# rapidshark-main-breakout-mk-1_0.net
KiCad netlist of a schematic drawn in EAGLE
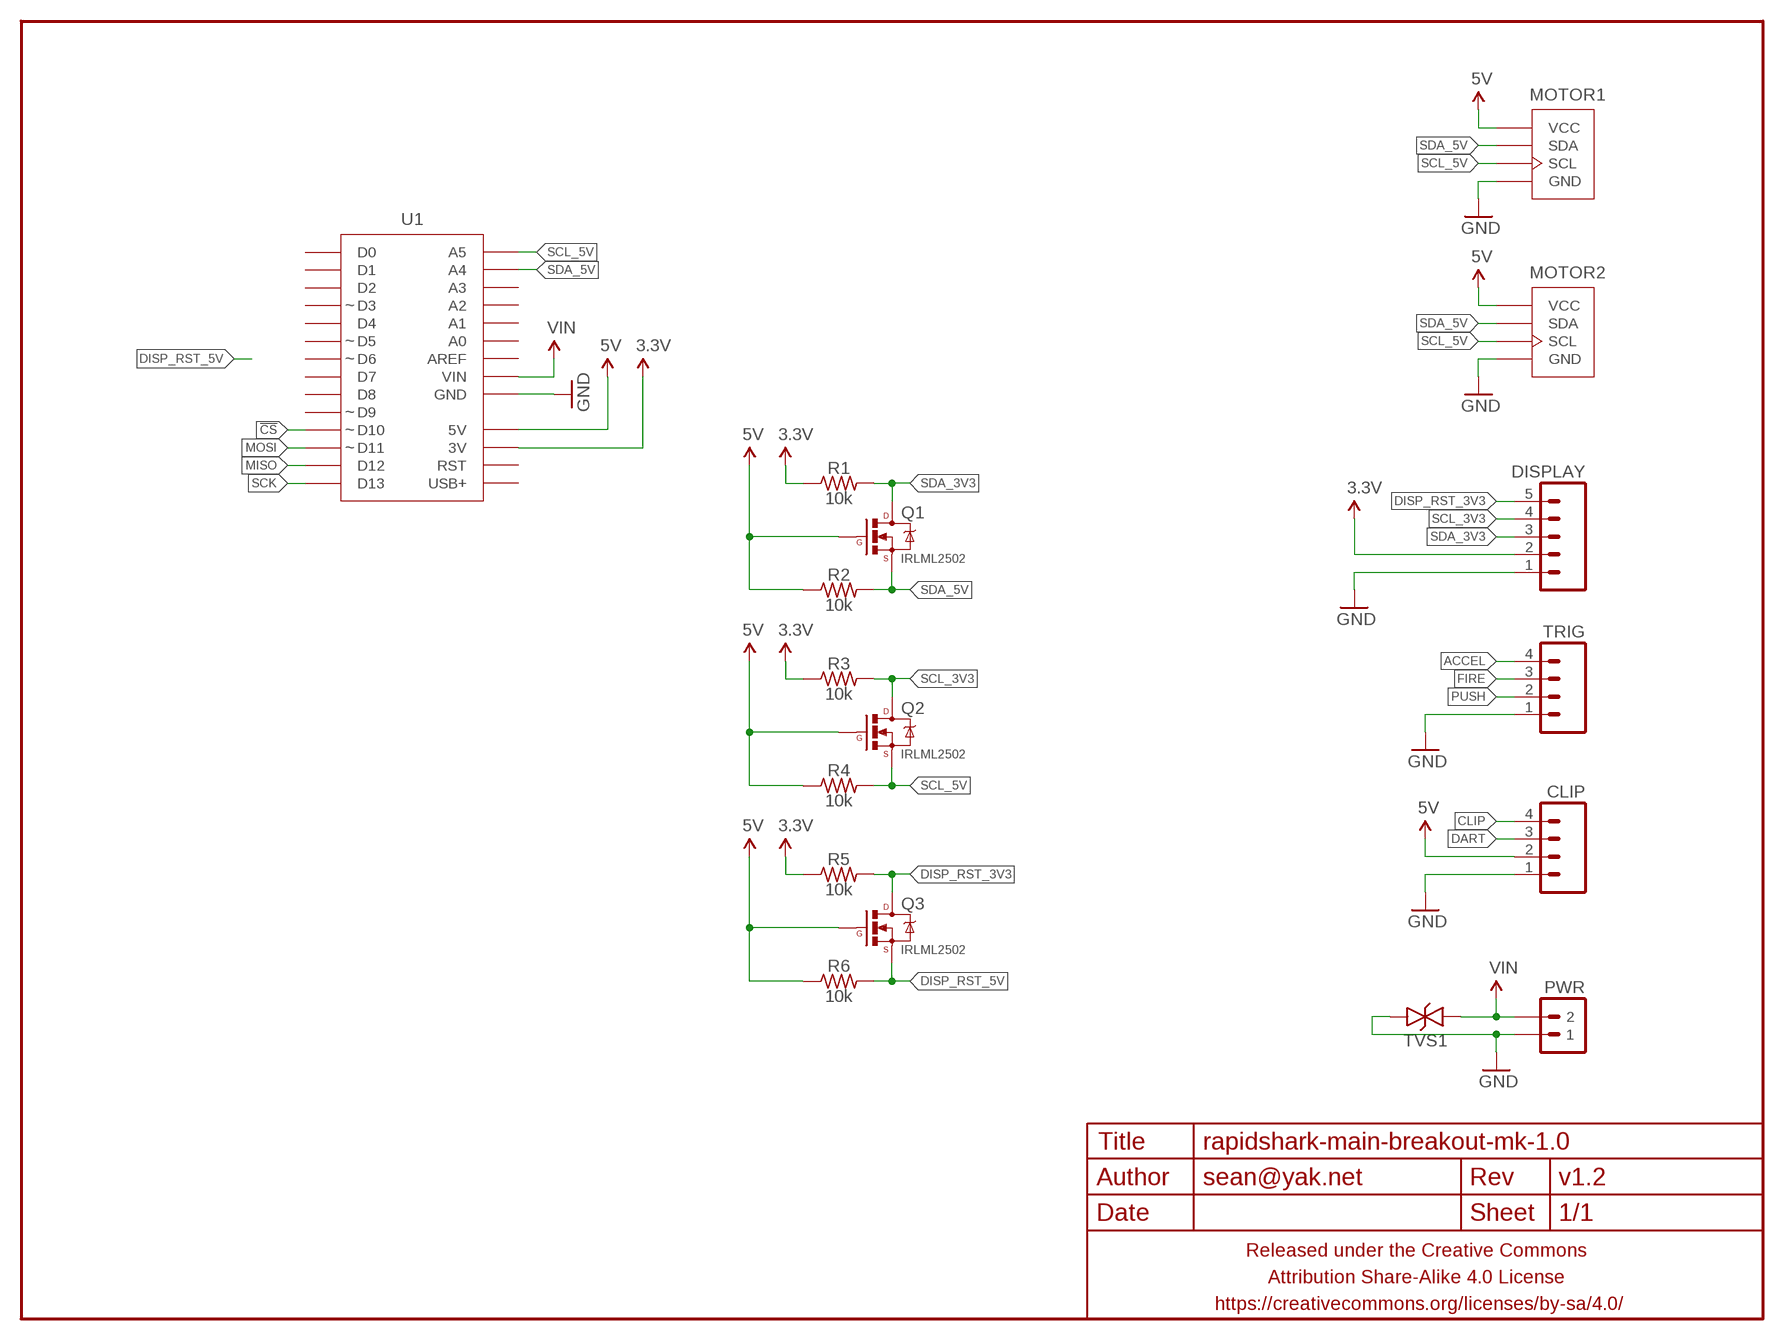
[diagram p0: schematic, sheet 1]

(export (version "E")
  (design (tool "Eeschema 10.0.6"))
  (components
    (comp (ref "CLIP")
      (value "M04JST-PTH-VERT")
      (footprint "eagle-import:JST-4-PH-VERT-PTH")
      (libsource (lib "eagle-import") (part "M04JST-PTH-VERT"))
    )
    (comp (ref "DISPLAY")
      (value "M05JST-PH-VERT-PTH")
      (footprint "eagle-import:JST-5-PH-VERT-PTH")
      (libsource (lib "eagle-import") (part "M05JST-PH-VERT-PTH"))
    )
    (comp (ref "FRAME1")
      (value "FRAME-LETTERNO_PACKAGE")
      (footprint "eagle-import:DUMMY")
      (fields (field (name "DESIGNER") "sean@yak.net") (field (name "VERSION") "v1.2"))
      (libsource (lib "eagle-import") (part "FRAME-LETTERNO_PACKAGE"))
    )
    (comp (ref "MOTOR1")
      (value "M04-I2CJST-4-PH-VERT-NS")
      (footprint "eagle-import:JST-4-PH-VERT-PTH")
      (libsource (lib "eagle-import") (part "M04-I2CJST-4-PH-VERT-NS"))
    )
    (comp (ref "MOTOR2")
      (value "M04-I2CJST-4-PH-VERT-NS")
      (footprint "eagle-import:JST-4-PH-VERT-PTH")
      (libsource (lib "eagle-import") (part "M04-I2CJST-4-PH-VERT-NS"))
    )
    (comp (ref "PWR")
      (value "M02PTH-CENTERED-R+")
      (footprint "eagle-import:1X02-CENTER-R+")
      (libsource (lib "eagle-import") (part "M02PTH-CENTERED-R+"))
    )
    (comp (ref "Q1")
      (value "IRLML2502")
      (footprint "eagle-import:SOT23")
      (libsource (lib "eagle-import") (part "MOSFET-NCHANNELIRLML2502"))
    )
    (comp (ref "Q2")
      (value "IRLML2502")
      (footprint "eagle-import:SOT23")
      (libsource (lib "eagle-import") (part "MOSFET-NCHANNELIRLML2502"))
    )
    (comp (ref "Q3")
      (value "IRLML2502")
      (footprint "eagle-import:SOT23")
      (libsource (lib "eagle-import") (part "MOSFET-NCHANNELIRLML2502"))
    )
    (comp (ref "R1")
      (value "10k")
      (footprint "eagle-import:R0603")
      (libsource (lib "eagle-import") (part "RESISTORR0603"))
    )
    (comp (ref "R2")
      (value "10k")
      (footprint "eagle-import:R0603")
      (libsource (lib "eagle-import") (part "RESISTORR0603"))
    )
    (comp (ref "R3")
      (value "10k")
      (footprint "eagle-import:R0603")
      (libsource (lib "eagle-import") (part "RESISTORR0603"))
    )
    (comp (ref "R4")
      (value "10k")
      (footprint "eagle-import:R0603")
      (libsource (lib "eagle-import") (part "RESISTORR0603"))
    )
    (comp (ref "R5")
      (value "10k")
      (footprint "eagle-import:R0603")
      (libsource (lib "eagle-import") (part "RESISTORR0603"))
    )
    (comp (ref "R6")
      (value "10k")
      (footprint "eagle-import:R0603")
      (libsource (lib "eagle-import") (part "RESISTORR0603"))
    )
    (comp (ref "TRIG")
      (value "M04JST-PTH-VERT")
      (footprint "eagle-import:JST-4-PH-VERT-PTH")
      (libsource (lib "eagle-import") (part "M04JST-PTH-VERT"))
    )
    (comp (ref "TVS1")
      (value "TVSSMA")
      (footprint "eagle-import:SMA-DIODE-TVS-BIDIR")
      (libsource (lib "eagle-import") (part "TVSSMA"))
    )
    (comp (ref "U1")
      (value "ADAFRUIT_METRO_MINISMD-NOHOLES")
      (footprint "eagle-import:ADAFRUIT_METRO_MINI_SMD")
      (libsource (lib "eagle-import") (part "ADAFRUIT_METRO_MINISMD-NOHOLES"))
    )
  )
  (nets
    (net (code "1") (name "/~{CS}") (class "Default")
      (node (ref "U1") (pin "11") (pinfunction "D10_11") (pintype "bidirectional"))
    )
    (net (code "2") (name "3.3V") (class "Default")
      (node (ref "DISPLAY") (pin "2") (pinfunction "2_2") (pintype "passive"))
      (node (ref "R1") (pin "1") (pinfunction "1_1") (pintype "passive"))
      (node (ref "R3") (pin "1") (pinfunction "1_1") (pintype "passive"))
      (node (ref "R5") (pin "1") (pinfunction "1_1") (pintype "passive"))
      (node (ref "U1") (pin "17") (pinfunction "3V_17") (pintype "bidirectional"))
    )
    (net (code "3") (name "5V") (class "Default")
      (node (ref "CLIP") (pin "2") (pinfunction "2_2") (pintype "passive"))
      (node (ref "MOTOR1") (pin "2") (pinfunction "VCC_2") (pintype "bidirectional"))
      (node (ref "MOTOR2") (pin "2") (pinfunction "VCC_2") (pintype "bidirectional"))
      (node (ref "Q1") (pin "1") (pinfunction "G_1") (pintype "passive"))
      (node (ref "Q2") (pin "1") (pinfunction "G_1") (pintype "passive"))
      (node (ref "Q3") (pin "1") (pinfunction "G_1") (pintype "passive"))
      (node (ref "R2") (pin "1") (pinfunction "1_1") (pintype "passive"))
      (node (ref "R4") (pin "1") (pinfunction "1_1") (pintype "passive"))
      (node (ref "R6") (pin "1") (pinfunction "1_1") (pintype "passive"))
      (node (ref "U1") (pin "18") (pinfunction "5V_18") (pintype "bidirectional"))
    )
    (net (code "4") (name "ACCEL") (class "Default")
      (node (ref "TRIG") (pin "4") (pinfunction "4_4") (pintype "passive"))
    )
    (net (code "5") (name "CLIP") (class "Default")
      (node (ref "CLIP") (pin "4") (pinfunction "4_4") (pintype "passive"))
    )
    (net (code "6") (name "DART") (class "Default")
      (node (ref "CLIP") (pin "3") (pinfunction "3_3") (pintype "passive"))
    )
    (net (code "7") (name "DISP_RST_3V3") (class "Default")
      (node (ref "DISPLAY") (pin "5") (pinfunction "5_5") (pintype "passive"))
      (node (ref "Q3") (pin "3") (pinfunction "D_3") (pintype "passive"))
      (node (ref "R5") (pin "2") (pinfunction "2_2") (pintype "passive"))
    )
    (net (code "8") (name "DISP_RST_5V") (class "Default")
      (node (ref "Q3") (pin "2") (pinfunction "S_2") (pintype "passive"))
      (node (ref "R6") (pin "2") (pinfunction "2_2") (pintype "passive"))
    )
    (net (code "9") (name "FIRE") (class "Default")
      (node (ref "TRIG") (pin "3") (pinfunction "3_3") (pintype "passive"))
    )
    (net (code "10") (name "GND") (class "Default")
      (node (ref "CLIP") (pin "1") (pinfunction "1_1") (pintype "passive"))
      (node (ref "DISPLAY") (pin "1") (pinfunction "1_1") (pintype "passive"))
      (node (ref "MOTOR1") (pin "1") (pinfunction "GND_1") (pintype "bidirectional"))
      (node (ref "MOTOR2") (pin "1") (pinfunction "GND_1") (pintype "bidirectional"))
      (node (ref "PWR") (pin "1") (pinfunction "1_1") (pintype "passive"))
      (node (ref "TRIG") (pin "1") (pinfunction "1_1") (pintype "passive"))
      (node (ref "TVS1") (pin "2") (pinfunction "2_2") (pintype "passive"))
      (node (ref "U1") (pin "19") (pinfunction "GND_19") (pintype "bidirectional"))
      (node (ref "U1") (pin "20") (pinfunction "GND_20") (pintype "bidirectional"))
    )
    (net (code "11") (name "MISO") (class "Default")
      (node (ref "U1") (pin "13") (pinfunction "D12_13") (pintype "bidirectional"))
    )
    (net (code "12") (name "MOSI") (class "Default")
      (node (ref "U1") (pin "12") (pinfunction "D11_12") (pintype "bidirectional"))
    )
    (net (code "13") (name "PUSH") (class "Default")
      (node (ref "TRIG") (pin "2") (pinfunction "2_2") (pintype "passive"))
    )
    (net (code "14") (name "SCK") (class "Default")
      (node (ref "U1") (pin "14") (pinfunction "D13_14") (pintype "bidirectional"))
    )
    (net (code "15") (name "SCL_3V3") (class "Default")
      (node (ref "DISPLAY") (pin "4") (pinfunction "4_4") (pintype "passive"))
      (node (ref "Q2") (pin "3") (pinfunction "D_3") (pintype "passive"))
      (node (ref "R3") (pin "2") (pinfunction "2_2") (pintype "passive"))
    )
    (net (code "16") (name "SCL_5V") (class "Default")
      (node (ref "MOTOR1") (pin "4") (pinfunction "SCL_4") (pintype "bidirectional"))
      (node (ref "MOTOR2") (pin "4") (pinfunction "SCL_4") (pintype "bidirectional"))
      (node (ref "Q2") (pin "2") (pinfunction "S_2") (pintype "passive"))
      (node (ref "R4") (pin "2") (pinfunction "2_2") (pintype "passive"))
      (node (ref "U1") (pin "28") (pinfunction "A5_28") (pintype "bidirectional"))
    )
    (net (code "17") (name "SDA_3V3") (class "Default")
      (node (ref "DISPLAY") (pin "3") (pinfunction "3_3") (pintype "passive"))
      (node (ref "Q1") (pin "3") (pinfunction "D_3") (pintype "passive"))
      (node (ref "R1") (pin "2") (pinfunction "2_2") (pintype "passive"))
    )
    (net (code "18") (name "SDA_5V") (class "Default")
      (node (ref "MOTOR1") (pin "3") (pinfunction "SDA_3") (pintype "bidirectional"))
      (node (ref "MOTOR2") (pin "3") (pinfunction "SDA_3") (pintype "bidirectional"))
      (node (ref "Q1") (pin "2") (pinfunction "S_2") (pintype "passive"))
      (node (ref "R2") (pin "2") (pinfunction "2_2") (pintype "passive"))
      (node (ref "U1") (pin "27") (pinfunction "A4_27") (pintype "bidirectional"))
    )
    (net (code "19") (name "VIN") (class "Default")
      (node (ref "PWR") (pin "2") (pinfunction "2_2") (pintype "passive"))
      (node (ref "TVS1") (pin "1") (pinfunction "1_1") (pintype "passive"))
      (node (ref "U1") (pin "21") (pinfunction "VIN_21") (pintype "bidirectional"))
    )
    (net (code "20") (name "unconnected-(U1-A0-Pad23)") (class "Default")
      (node (ref "U1") (pin "23") (pinfunction "A0_23") (pintype "bidirectional"))
    )
    (net (code "21") (name "unconnected-(U1-A1-Pad24)") (class "Default")
      (node (ref "U1") (pin "24") (pinfunction "A1_24") (pintype "bidirectional"))
    )
    (net (code "22") (name "unconnected-(U1-A2-Pad25)") (class "Default")
      (node (ref "U1") (pin "25") (pinfunction "A2_25") (pintype "bidirectional"))
    )
    (net (code "23") (name "unconnected-(U1-A3-Pad26)") (class "Default")
      (node (ref "U1") (pin "26") (pinfunction "A3_26") (pintype "bidirectional"))
    )
    (net (code "24") (name "unconnected-(U1-AREF-Pad22)") (class "Default")
      (node (ref "U1") (pin "22") (pinfunction "AREF_22") (pintype "bidirectional"))
    )
    (net (code "25") (name "unconnected-(U1-D0-Pad1)") (class "Default")
      (node (ref "U1") (pin "1") (pinfunction "D0_1") (pintype "bidirectional"))
    )
    (net (code "26") (name "unconnected-(U1-D1-Pad2)") (class "Default")
      (node (ref "U1") (pin "2") (pinfunction "D1_2") (pintype "bidirectional"))
    )
    (net (code "27") (name "unconnected-(U1-D2-Pad3)") (class "Default")
      (node (ref "U1") (pin "3") (pinfunction "D2_3") (pintype "bidirectional"))
    )
    (net (code "28") (name "unconnected-(U1-D3-Pad4)") (class "Default")
      (node (ref "U1") (pin "4") (pinfunction "D3_4") (pintype "bidirectional"))
    )
    (net (code "29") (name "unconnected-(U1-D4-Pad5)") (class "Default")
      (node (ref "U1") (pin "5") (pinfunction "D4_5") (pintype "bidirectional"))
    )
    (net (code "30") (name "unconnected-(U1-D5-Pad6)") (class "Default")
      (node (ref "U1") (pin "6") (pinfunction "D5_6") (pintype "bidirectional"))
    )
    (net (code "31") (name "unconnected-(U1-D6-Pad7)") (class "Default")
      (node (ref "U1") (pin "7") (pinfunction "D6_7") (pintype "bidirectional"))
    )
    (net (code "32") (name "unconnected-(U1-D7-Pad8)") (class "Default")
      (node (ref "U1") (pin "8") (pinfunction "D7_8") (pintype "bidirectional"))
    )
    (net (code "33") (name "unconnected-(U1-D8-Pad9)") (class "Default")
      (node (ref "U1") (pin "9") (pinfunction "D8_9") (pintype "bidirectional"))
    )
    (net (code "34") (name "unconnected-(U1-D9-Pad10)") (class "Default")
      (node (ref "U1") (pin "10") (pinfunction "D9_10") (pintype "bidirectional"))
    )
    (net (code "35") (name "unconnected-(U1-RST-Pad16)") (class "Default")
      (node (ref "U1") (pin "16") (pinfunction "RST_16") (pintype "bidirectional"))
    )
    (net (code "36") (name "unconnected-(U1-USB+-Pad15)") (class "Default")
      (node (ref "U1") (pin "15") (pinfunction "USB+_15") (pintype "bidirectional"))
    )
  )
)
